# SCH_ESP-RotaryCell-Main-Carrier-Rev-A1_2.net
KiCad netlist of a schematic drawn in EasyEDA
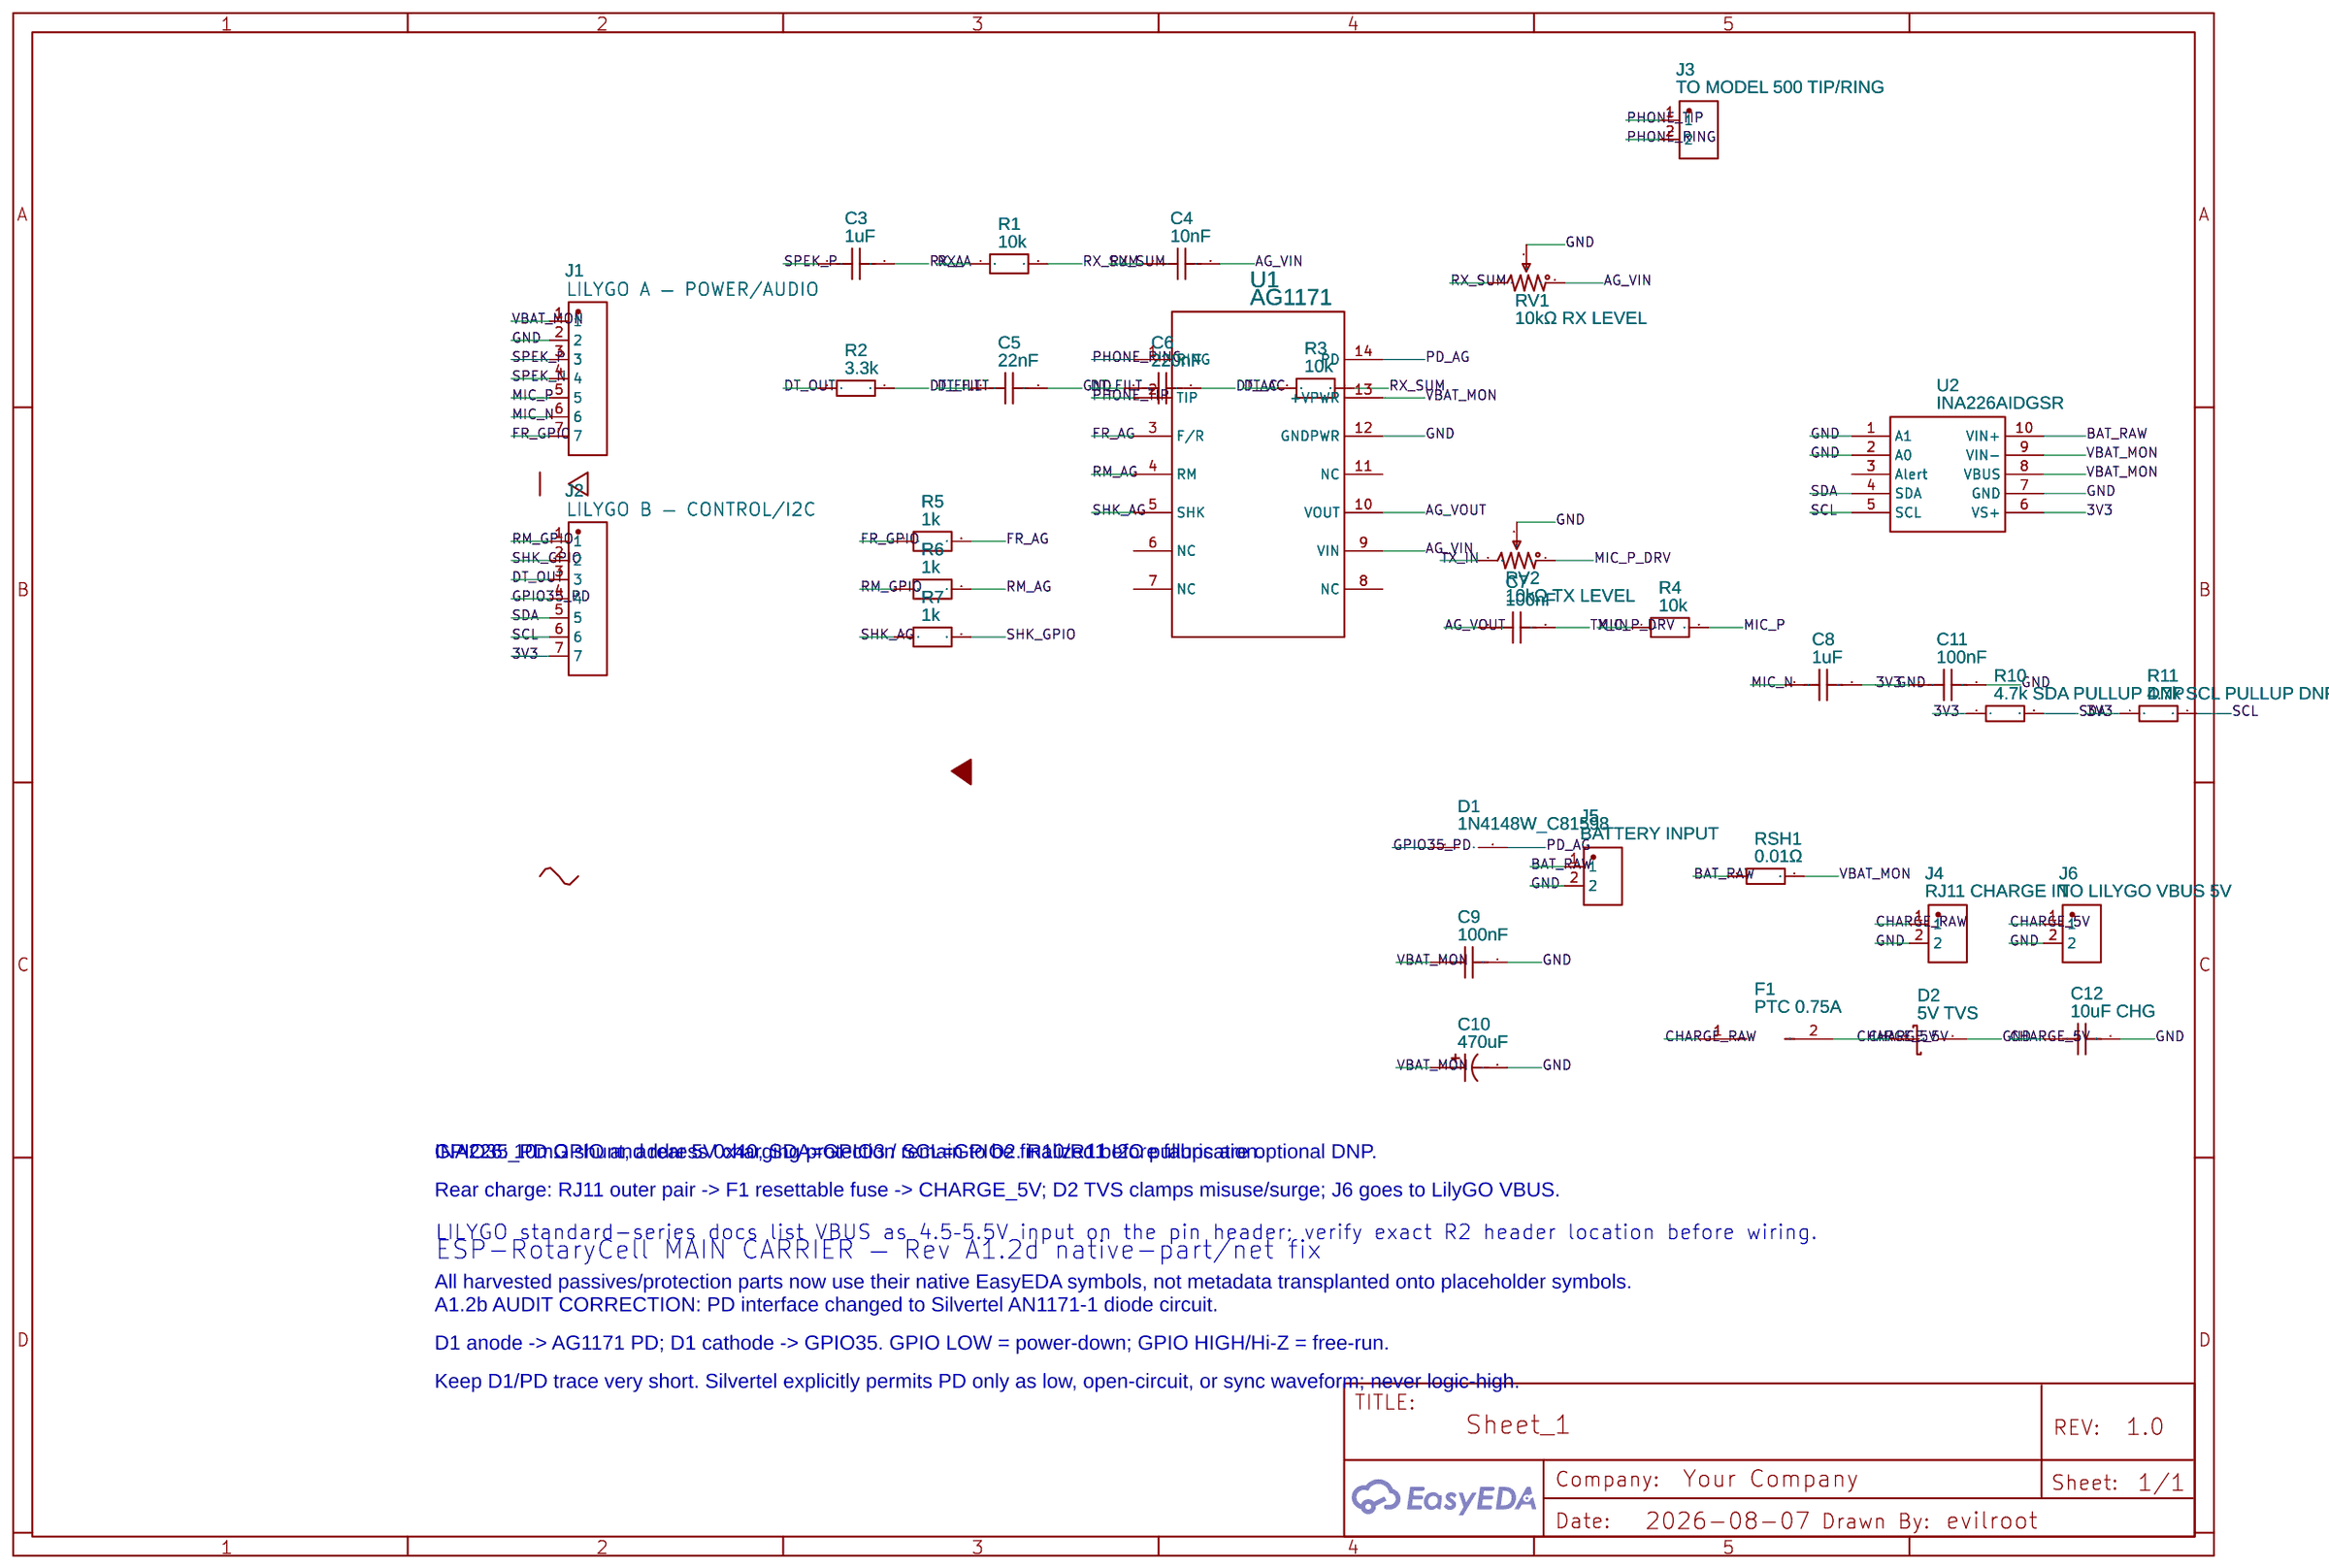
[diagram p0: schematic sheet]

(export (version "E")
  (design (tool "Eeschema 10.0.6"))
  (components
    (comp (ref "C3")
      (value "1uF")
      (fields
        (field (name "Manufacturer Part") "C0805C105K5RACAUTO")
        (field (name "Manufacturer") "KEMET(基美)")
      )
      (libsource (lib "") (part "C0805C105K5RACAUTO"))
    )
    (comp (ref "C4")
      (value "10nF")
      (fields
        (field (name "Manufacturer Part") "CGA0805X7R103J500KT")
        (field (name "Manufacturer") "HRE(芯声)")
      )
      (libsource (lib "") (part "CGA0805X7R103J500KT"))
    )
    (comp (ref "C5")
      (value "22nF")
      (fields
        (field (name "Manufacturer Part") "CGA0805C0G223J500MT")
        (field (name "Manufacturer") "HRE(芯声)")
      )
      (libsource (lib "") (part "CGA0805C0G223J500MT"))
    )
    (comp (ref "C6")
      (value "220nF")
      (fields
        (field (name "Manufacturer Part") "CGA0805X7R224K101MT")
        (field (name "Manufacturer") "HRE(芯声)")
      )
      (libsource (lib "") (part "CGA0805X7R224K101MT"))
    )
    (comp (ref "C7")
      (value "100nF")
      (fields
        (field (name "Manufacturer Part") "CAI0805X7R104K500KT")
        (field (name "Manufacturer") "HRE(芯声)")
      )
      (libsource (lib "") (part "CAI0805X7R104K500KT"))
    )
    (comp (ref "C8")
      (value "1uF")
      (fields
        (field (name "Manufacturer Part") "C0805C105K5RACAUTO")
        (field (name "Manufacturer") "KEMET(基美)")
      )
      (libsource (lib "") (part "C0805C105K5RACAUTO"))
    )
    (comp (ref "C9")
      (value "100nF")
      (fields
        (field (name "Manufacturer Part") "CAI0805X7R104K500KT")
        (field (name "Manufacturer") "HRE(芯声)")
      )
      (libsource (lib "") (part "CAI0805X7R104K500KT"))
    )
    (comp (ref "C10")
      (value "470uF")
      (fields
        (field (name "Manufacturer Part") "RYHT16V470UF5.5*11")
        (field (name "Manufacturer") "HONOR(荣誉)")
      )
      (libsource (lib "") (part "RYHT16V470UF5.5*11"))
    )
    (comp (ref "C11")
      (value "100nF")
      (fields
        (field (name "Manufacturer Part") "CAI0805X7R104K500KT")
        (field (name "Manufacturer") "HRE(芯声)")
      )
      (libsource (lib "") (part "CAI0805X7R104K500KT"))
    )
    (comp (ref "C12")
      (value "10uF CHG")
      (fields
        (field (name "Manufacturer Part") "CGA0805X5R106K160MT")
        (field (name "Manufacturer") "HRE(芯声)")
      )
      (libsource (lib "") (part "CGA0805X5R106K160MT"))
    )
    (comp (ref "D1")
      (value "1N4148W_C81598")
      (fields (field (name "Manufacturer Part") "1N4148W") (field (name "Manufacturer") "ST(先科)"))
      (libsource (lib "") (part "1N4148W_C81598"))
    )
    (comp (ref "D2")
      (value "5V TVS")
      (fields (field (name "Manufacturer Part") "SMA6.0A_TVS6V"))
      (libsource (lib "") (part "SMA6.0A_TVS6V"))
    )
    (comp (ref "F1")
      (value "PTC 0.75A")
      (fields (field (name "Manufacturer Part") "PPTCNANOSMDC075F-20.75A6V"))
      (libsource (lib "") (part "PPTCNANOSMDC075F-20.75A6V"))
    )
    (comp (ref "J1")
      (value "LILYGO A — POWER/AUDIO")
      (fields
        (field (name "Manufacturer Part") "PM2.54-1x7PZZ-H8.5")
        (field (name "Manufacturer") "SHOU HAN(首韩)")
      )
      (libsource (lib "") (part "PM2.54-1X7PZZ-H8.5"))
    )
    (comp (ref "J2")
      (value "LILYGO B — CONTROL/I2C")
      (fields
        (field (name "Manufacturer Part") "PM2.54-1x7PZZ-H8.5")
        (field (name "Manufacturer") "SHOU HAN(首韩)")
      )
      (libsource (lib "") (part "PM2.54-1X7PZZ-H8.5"))
    )
    (comp (ref "J3")
      (value "TO MODEL 500 TIP/RING")
      (fields
        (field (name "Manufacturer Part") "HMT-2.54-1*2PM")
        (field (name "Manufacturer") "HMTCONN(华明通)")
      )
      (libsource (lib "") (part "HMT-2.54-1*2PM"))
    )
    (comp (ref "J4")
      (value "RJ11 CHARGE IN")
      (fields
        (field (name "Manufacturer Part") "HMT-2.54-1*2PM")
        (field (name "Manufacturer") "HMTCONN(华明通)")
      )
      (libsource (lib "") (part "HMT-2.54-1*2PM"))
    )
    (comp (ref "J5")
      (value "BATTERY INPUT")
      (fields
        (field (name "Manufacturer Part") "HMT-2.54-1*2PM")
        (field (name "Manufacturer") "HMTCONN(华明通)")
      )
      (libsource (lib "") (part "HMT-2.54-1*2PM"))
    )
    (comp (ref "J6")
      (value "TO LILYGO VBUS 5V")
      (fields
        (field (name "Manufacturer Part") "HMT-2.54-1*2PM")
        (field (name "Manufacturer") "HMTCONN(华明通)")
      )
      (libsource (lib "") (part "HMT-2.54-1*2PM"))
    )
    (comp (ref "R1")
      (value "10k")
      (fields (field (name "Manufacturer Part") "RCS080510K0FKEA") (field (name "Manufacturer") "VISHAY(威世)"))
      (libsource (lib "") (part "RCS080510K0FKEA"))
    )
    (comp (ref "R2")
      (value "3.3k")
      (fields (field (name "Manufacturer Part") "RMC08053.3K1%N") (field (name "Manufacturer") "Tyohm(幸亚电阻)"))
      (libsource (lib "") (part "RMC08053.3K1%N"))
    )
    (comp (ref "R3")
      (value "10k")
      (fields (field (name "Manufacturer Part") "RCS080510K0FKEA") (field (name "Manufacturer") "VISHAY(威世)"))
      (libsource (lib "") (part "RCS080510K0FKEA"))
    )
    (comp (ref "R4")
      (value "10k")
      (fields (field (name "Manufacturer Part") "RCS080510K0FKEA") (field (name "Manufacturer") "VISHAY(威世)"))
      (libsource (lib "") (part "RCS080510K0FKEA"))
    )
    (comp (ref "R5")
      (value "1k")
      (fields (field (name "Manufacturer Part") "CL0805JN1KPS") (field (name "Manufacturer") "昶龙科技"))
      (libsource (lib "") (part "CL0805JN1KPS"))
    )
    (comp (ref "R6")
      (value "1k")
      (fields (field (name "Manufacturer Part") "CL0805JN1KPS") (field (name "Manufacturer") "昶龙科技"))
      (libsource (lib "") (part "CL0805JN1KPS"))
    )
    (comp (ref "R7")
      (value "1k")
      (fields (field (name "Manufacturer Part") "CL0805JN1KPS") (field (name "Manufacturer") "昶龙科技"))
      (libsource (lib "") (part "CL0805JN1KPS"))
    )
    (comp (ref "R10")
      (value "4.7k SDA PULLUP DNP")
      (fields (field (name "Manufacturer Part") "RMC08054.7K1%N") (field (name "Manufacturer") "Tyohm(幸亚电阻)"))
      (libsource (lib "") (part "RMC08054.7K1%N"))
    )
    (comp (ref "R11")
      (value "4.7k SCL PULLUP DNP")
      (fields (field (name "Manufacturer Part") "RMC08054.7K1%N") (field (name "Manufacturer") "Tyohm(幸亚电阻)"))
      (libsource (lib "") (part "RMC08054.7K1%N"))
    )
    (comp (ref "RSH1")
      (value "0.01Ω")
      (fields (field (name "Manufacturer Part") "MRF6432(2512)LR010JTS") (field (name "Manufacturer") "SUP"))
      (libsource (lib "") (part "MRF6432(2512)LR010JTS"))
    )
    (comp (ref "RV1")
      (value "10kΩ RX LEVEL")
      (fields (field (name "Manufacturer Part") "PS10KV50-103A3030") (field (name "Manufacturer") "Amphenol"))
      (libsource (lib "") (part "PS10KV50-103A3030"))
    )
    (comp (ref "RV2")
      (value "10kΩ TX LEVEL")
      (fields (field (name "Manufacturer Part") "PS10KV50-103A3030") (field (name "Manufacturer") "Amphenol"))
      (libsource (lib "") (part "PS10KV50-103A3030"))
    )
    (comp (ref "U1")
      (value "AG1171")
      (fields (field (name "Manufacturer Part") "Ag1171") (field (name "Manufacturer") "Silver Telecom"))
      (libsource (lib "") (part "AG1171"))
    )
    (comp (ref "U2")
      (value "INA226AIDGSR")
      (fields (field (name "Manufacturer") "TI(德州仪器)"))
      (libsource (lib "") (part "INA226AIDGSR"))
    )
  )
  (nets
    (net (code "1") (name "/3V3") (class "Default")
      (node (ref "C10") (pin "2") (pinfunction "2_2") (pintype "input"))
      (node (ref "C11") (pin "1") (pinfunction "1_1") (pintype "unspecified"))
      (node (ref "C11") (pin "2") (pinfunction "2_2") (pintype "unspecified"))
      (node (ref "C12") (pin "2") (pinfunction "2_2") (pintype "unspecified"))
      (node (ref "C5") (pin "2") (pinfunction "2_2") (pintype "unspecified"))
      (node (ref "C8") (pin "2") (pinfunction "2_2") (pintype "unspecified"))
      (node (ref "C9") (pin "2") (pinfunction "2_2") (pintype "unspecified"))
      (node (ref "D2") (pin "2") (pinfunction "A_2") (pintype "unspecified"))
      (node (ref "J1") (pin "2") (pinfunction "2_2") (pintype "unspecified"))
      (node (ref "J2") (pin "7") (pinfunction "7_7") (pintype "unspecified"))
      (node (ref "J4") (pin "2") (pinfunction "2_2") (pintype "unspecified"))
      (node (ref "J5") (pin "2") (pinfunction "2_2") (pintype "unspecified"))
      (node (ref "J6") (pin "2") (pinfunction "2_2") (pintype "unspecified"))
      (node (ref "R10") (pin "1") (pinfunction "1_1") (pintype "unspecified"))
      (node (ref "R11") (pin "1") (pinfunction "1_1") (pintype "unspecified"))
      (node (ref "RV1") (pin "3") (pinfunction "3_3") (pintype "unspecified"))
      (node (ref "RV2") (pin "3") (pinfunction "3_3") (pintype "unspecified"))
      (node (ref "U1") (pin "12") (pinfunction "GNDPWR_12") (pintype "unspecified"))
      (node (ref "U2") (pin "1") (pinfunction "A1_1") (pintype "unspecified"))
      (node (ref "U2") (pin "2") (pinfunction "A0_2") (pintype "unspecified"))
      (node (ref "U2") (pin "6") (pinfunction "VS+_6") (pintype "unspecified"))
      (node (ref "U2") (pin "7") (pinfunction "GND_7") (pintype "unspecified"))
    )
    (net (code "2") (name "/AG_VIN") (class "Default")
      (node (ref "C4") (pin "2") (pinfunction "2_2") (pintype "unspecified"))
      (node (ref "RV1") (pin "2") (pinfunction "2_2") (pintype "unspecified"))
      (node (ref "U1") (pin "9") (pinfunction "VIN_9") (pintype "unspecified"))
    )
    (net (code "3") (name "/AG_VOUT") (class "Default")
      (node (ref "C7") (pin "1") (pinfunction "1_1") (pintype "unspecified"))
      (node (ref "U1") (pin "10") (pinfunction "VOUT_10") (pintype "unspecified"))
    )
    (net (code "4") (name "/BAT_RAW") (class "Default")
      (node (ref "J5") (pin "1") (pinfunction "1_1") (pintype "unspecified"))
      (node (ref "RSH1") (pin "1") (pinfunction "1_1") (pintype "input"))
      (node (ref "U2") (pin "10") (pinfunction "VIN+_10") (pintype "unspecified"))
    )
    (net (code "5") (name "/CHARGE_5V") (class "Default")
      (node (ref "C12") (pin "1") (pinfunction "1_1") (pintype "unspecified"))
      (node (ref "D2") (pin "1") (pinfunction "C_1") (pintype "unspecified"))
      (node (ref "F1") (pin "2") (pinfunction "2_2") (pintype "unspecified"))
      (node (ref "J6") (pin "1") (pinfunction "1_1") (pintype "unspecified"))
    )
    (net (code "6") (name "/CHARGE_RAW") (class "Default")
      (node (ref "F1") (pin "1") (pinfunction "1_1") (pintype "unspecified"))
      (node (ref "J4") (pin "1") (pinfunction "1_1") (pintype "unspecified"))
    )
    (net (code "7") (name "/DT_AC") (class "Default")
      (node (ref "C6") (pin "2") (pinfunction "2_2") (pintype "unspecified"))
      (node (ref "R3") (pin "1") (pinfunction "1_1") (pintype "unspecified"))
    )
    (net (code "8") (name "/DT_FILT") (class "Default")
      (node (ref "C5") (pin "1") (pinfunction "1_1") (pintype "unspecified"))
      (node (ref "C6") (pin "1") (pinfunction "1_1") (pintype "unspecified"))
      (node (ref "R2") (pin "2") (pinfunction "2_2") (pintype "unspecified"))
    )
    (net (code "9") (name "/DT_OUT") (class "Default")
      (node (ref "J2") (pin "3") (pinfunction "3_3") (pintype "unspecified"))
      (node (ref "R2") (pin "1") (pinfunction "1_1") (pintype "unspecified"))
    )
    (net (code "10") (name "/FR_AG") (class "Default")
      (node (ref "R5") (pin "2") (pinfunction "2_2") (pintype "unspecified"))
      (node (ref "U1") (pin "3") (pinfunction "F/R_3") (pintype "unspecified"))
    )
    (net (code "11") (name "/FR_GPIO") (class "Default")
      (node (ref "J1") (pin "7") (pinfunction "7_7") (pintype "unspecified"))
      (node (ref "R5") (pin "1") (pinfunction "1_1") (pintype "unspecified"))
    )
    (net (code "12") (name "/GPIO35_PD") (class "Default")
      (node (ref "D1") (pin "1") (pinfunction "K_1") (pintype "unspecified"))
      (node (ref "J2") (pin "4") (pinfunction "4_4") (pintype "unspecified"))
    )
    (net (code "13") (name "/MIC_N") (class "Default")
      (node (ref "C8") (pin "1") (pinfunction "1_1") (pintype "unspecified"))
      (node (ref "J1") (pin "6") (pinfunction "6_6") (pintype "unspecified"))
    )
    (net (code "14") (name "/MIC_P") (class "Default")
      (node (ref "J1") (pin "5") (pinfunction "5_5") (pintype "unspecified"))
      (node (ref "R4") (pin "2") (pinfunction "2_2") (pintype "unspecified"))
    )
    (net (code "15") (name "/MIC_P_DRV") (class "Default")
      (node (ref "R4") (pin "1") (pinfunction "1_1") (pintype "unspecified"))
      (node (ref "RV2") (pin "2") (pinfunction "2_2") (pintype "unspecified"))
    )
    (net (code "16") (name "/PD_AG") (class "Default")
      (node (ref "D1") (pin "2") (pinfunction "A_2") (pintype "unspecified"))
      (node (ref "U1") (pin "14") (pinfunction "PD_14") (pintype "unspecified"))
    )
    (net (code "17") (name "/PHONE_RING") (class "Default")
      (node (ref "J3") (pin "2") (pinfunction "2_2") (pintype "unspecified"))
      (node (ref "U1") (pin "1") (pinfunction "RING_1") (pintype "unspecified"))
    )
    (net (code "18") (name "/PHONE_TIP") (class "Default")
      (node (ref "J3") (pin "1") (pinfunction "1_1") (pintype "unspecified"))
      (node (ref "U1") (pin "2") (pinfunction "TIP_2") (pintype "unspecified"))
    )
    (net (code "19") (name "/RM_AG") (class "Default")
      (node (ref "R6") (pin "2") (pinfunction "2_2") (pintype "unspecified"))
      (node (ref "U1") (pin "4") (pinfunction "RM_4") (pintype "unspecified"))
    )
    (net (code "20") (name "/RM_GPIO") (class "Default")
      (node (ref "J2") (pin "1") (pinfunction "1_1") (pintype "unspecified"))
      (node (ref "R6") (pin "1") (pinfunction "1_1") (pintype "unspecified"))
    )
    (net (code "21") (name "/RX_A") (class "Default")
      (node (ref "C3") (pin "2") (pinfunction "2_2") (pintype "unspecified"))
      (node (ref "R1") (pin "1") (pinfunction "1_1") (pintype "unspecified"))
    )
    (net (code "22") (name "/RX_SUM") (class "Default")
      (node (ref "C4") (pin "1") (pinfunction "1_1") (pintype "unspecified"))
      (node (ref "R1") (pin "2") (pinfunction "2_2") (pintype "unspecified"))
      (node (ref "R3") (pin "2") (pinfunction "2_2") (pintype "unspecified"))
      (node (ref "RV1") (pin "1") (pinfunction "1_1") (pintype "unspecified"))
    )
    (net (code "23") (name "/SCL") (class "Default")
      (node (ref "J2") (pin "6") (pinfunction "6_6") (pintype "unspecified"))
      (node (ref "R11") (pin "2") (pinfunction "2_2") (pintype "unspecified"))
      (node (ref "U2") (pin "5") (pinfunction "SCL_5") (pintype "unspecified"))
    )
    (net (code "24") (name "/SDA") (class "Default")
      (node (ref "J2") (pin "5") (pinfunction "5_5") (pintype "unspecified"))
      (node (ref "R10") (pin "2") (pinfunction "2_2") (pintype "unspecified"))
      (node (ref "U2") (pin "4") (pinfunction "SDA_4") (pintype "unspecified"))
    )
    (net (code "25") (name "/SHK_AG") (class "Default")
      (node (ref "R7") (pin "1") (pinfunction "1_1") (pintype "unspecified"))
      (node (ref "U1") (pin "5") (pinfunction "SHK_5") (pintype "unspecified"))
    )
    (net (code "26") (name "/SHK_GPIO") (class "Default")
      (node (ref "J2") (pin "2") (pinfunction "2_2") (pintype "unspecified"))
      (node (ref "R7") (pin "2") (pinfunction "2_2") (pintype "unspecified"))
    )
    (net (code "27") (name "/SPEK_N") (class "Default")
      (node (ref "J1") (pin "4") (pinfunction "4_4") (pintype "unspecified"))
    )
    (net (code "28") (name "/SPEK_P") (class "Default")
      (node (ref "C3") (pin "1") (pinfunction "1_1") (pintype "unspecified"))
      (node (ref "J1") (pin "3") (pinfunction "3_3") (pintype "unspecified"))
    )
    (net (code "29") (name "/TX_IN") (class "Default")
      (node (ref "C7") (pin "2") (pinfunction "2_2") (pintype "unspecified"))
      (node (ref "RV2") (pin "1") (pinfunction "1_1") (pintype "unspecified"))
    )
    (net (code "30") (name "/VBAT_MON") (class "Default")
      (node (ref "C10") (pin "1") (pinfunction "1_1") (pintype "input"))
      (node (ref "C9") (pin "1") (pinfunction "1_1") (pintype "unspecified"))
      (node (ref "J1") (pin "1") (pinfunction "1_1") (pintype "unspecified"))
      (node (ref "RSH1") (pin "2") (pinfunction "2_2") (pintype "input"))
      (node (ref "U1") (pin "13") (pinfunction "+VPWR_13") (pintype "unspecified"))
      (node (ref "U2") (pin "8") (pinfunction "VBUS_8") (pintype "unspecified"))
      (node (ref "U2") (pin "9") (pinfunction "VIN-_9") (pintype "unspecified"))
    )
    (net (code "31") (name "unconnected-(U1-NC-Pad6)") (class "Default")
      (node (ref "U1") (pin "6") (pinfunction "NC_6") (pintype "unspecified"))
    )
    (net (code "32") (name "unconnected-(U1-NC-Pad7)") (class "Default")
      (node (ref "U1") (pin "7") (pinfunction "NC_7") (pintype "unspecified"))
    )
    (net (code "33") (name "unconnected-(U1-NC-Pad8)") (class "Default")
      (node (ref "U1") (pin "8") (pinfunction "NC_8") (pintype "unspecified"))
    )
    (net (code "34") (name "unconnected-(U1-NC-Pad11)") (class "Default")
      (node (ref "U1") (pin "11") (pinfunction "NC_11") (pintype "unspecified"))
    )
    (net (code "35") (name "unconnected-(U2-Alert-Pad3)") (class "Default")
      (node (ref "U2") (pin "3") (pinfunction "Alert_3") (pintype "unspecified"))
    )
  )
)
